# Pressure_OUTPUT.net
KiCad netlist of a schematic drawn in Altium Designer
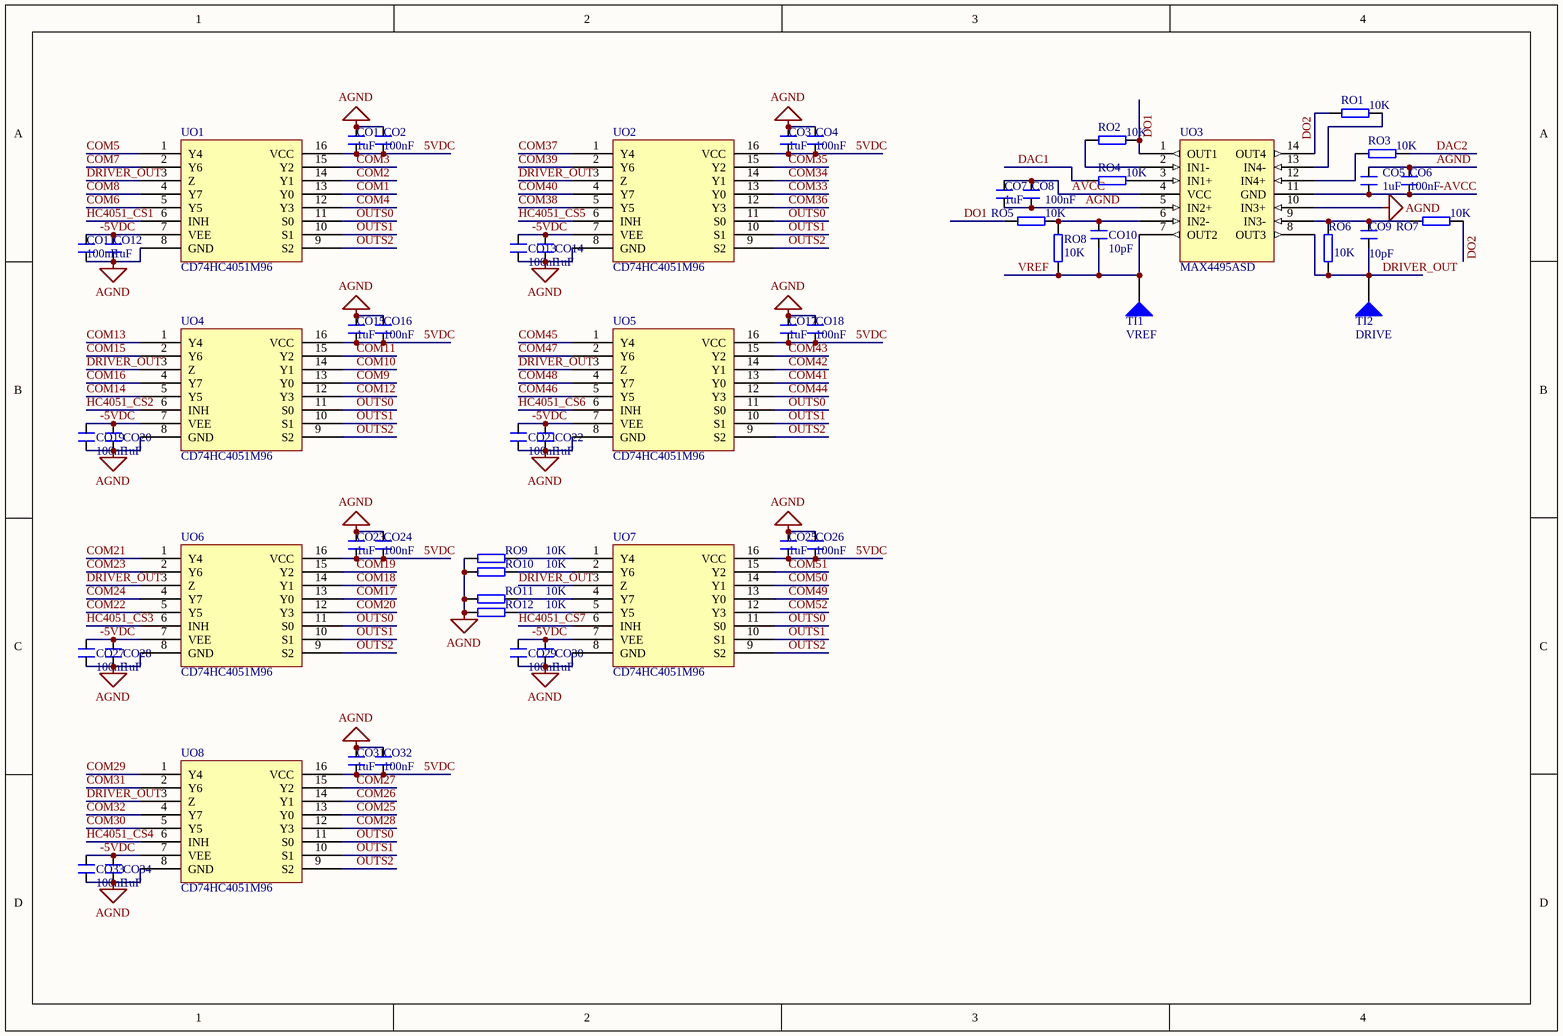
[diagram p0: Pressure_OUTPUT.SchDoc]

(export (version "E")
  (design (tool "Eeschema 10.0.6"))
  (components
    (comp (ref "CO1") (value "1uF") (footprint "C0603_HSC100") (libsource (lib "*") (part "CAP_M")))
    (comp (ref "CO2") (value "100nF") (footprint "C0603_HSC100") (libsource (lib "*") (part "CAP_M")))
    (comp (ref "CO3") (value "1uF") (footprint "C0603_HSC100") (libsource (lib "*") (part "CAP_M")))
    (comp (ref "CO4") (value "100nF") (footprint "C0603_HSC100") (libsource (lib "*") (part "CAP_M")))
    (comp (ref "CO5") (value "1uF") (footprint "C0603_HSC100") (libsource (lib "*") (part "CAP_M")))
    (comp (ref "CO6") (value "100nF") (footprint "C0603_HSC100") (libsource (lib "*") (part "CAP_M")))
    (comp (ref "CO7") (value "1uF") (footprint "C0603_HSC100") (libsource (lib "*") (part "CAP_M")))
    (comp (ref "CO8") (value "100nF") (footprint "C0603_HSC100") (libsource (lib "*") (part "CAP_M")))
    (comp (ref "CO9") (value "10pF") (footprint "C0603_HSC100") (libsource (lib "*") (part "CAP_M")))
    (comp (ref "CO10") (value "10pF") (footprint "C0603_HSC100") (libsource (lib "*") (part "CAP_M")))
    (comp (ref "CO11") (value "100nF") (footprint "C0603_HSC100") (libsource (lib "*") (part "CAP_M")))
    (comp (ref "CO12") (value "1uF") (footprint "C0603_HSC100") (libsource (lib "*") (part "CAP_M")))
    (comp (ref "CO13") (value "100nF") (footprint "C0603_HSC100") (libsource (lib "*") (part "CAP_M")))
    (comp (ref "CO14") (value "1uF") (footprint "C0603_HSC100") (libsource (lib "*") (part "CAP_M")))
    (comp (ref "CO15") (value "1uF") (footprint "C0603_HSC100") (libsource (lib "*") (part "CAP_M")))
    (comp (ref "CO16") (value "100nF") (footprint "C0603_HSC100") (libsource (lib "*") (part "CAP_M")))
    (comp (ref "CO17") (value "1uF") (footprint "C0603_HSC100") (libsource (lib "*") (part "CAP_M")))
    (comp (ref "CO18") (value "100nF") (footprint "C0603_HSC100") (libsource (lib "*") (part "CAP_M")))
    (comp (ref "CO19") (value "100nF") (footprint "C0603_HSC100") (libsource (lib "*") (part "CAP_M")))
    (comp (ref "CO20") (value "1uF") (footprint "C0603_HSC100") (libsource (lib "*") (part "CAP_M")))
    (comp (ref "CO21") (value "100nF") (footprint "C0603_HSC100") (libsource (lib "*") (part "CAP_M")))
    (comp (ref "CO22") (value "1uF") (footprint "C0603_HSC100") (libsource (lib "*") (part "CAP_M")))
    (comp (ref "CO23") (value "1uF") (footprint "C0603_HSC100") (libsource (lib "*") (part "CAP_M")))
    (comp (ref "CO24") (value "100nF") (footprint "C0603_HSC100") (libsource (lib "*") (part "CAP_M")))
    (comp (ref "CO25") (value "1uF") (footprint "C0603_HSC100") (libsource (lib "*") (part "CAP_M")))
    (comp (ref "CO26") (value "100nF") (footprint "C0603_HSC100") (libsource (lib "*") (part "CAP_M")))
    (comp (ref "CO27") (value "100nF") (footprint "C0603_HSC100") (libsource (lib "*") (part "CAP_M")))
    (comp (ref "CO28") (value "1uF") (footprint "C0603_HSC100") (libsource (lib "*") (part "CAP_M")))
    (comp (ref "CO29") (value "100nF") (footprint "C0603_HSC100") (libsource (lib "*") (part "CAP_M")))
    (comp (ref "CO30") (value "1uF") (footprint "C0603_HSC100") (libsource (lib "*") (part "CAP_M")))
    (comp (ref "CO31") (value "1uF") (footprint "C0603_HSC100") (libsource (lib "*") (part "CAP_M")))
    (comp (ref "CO32") (value "100nF") (footprint "C0603_HSC100") (libsource (lib "*") (part "CAP_M")))
    (comp (ref "CO33") (value "100nF") (footprint "C0603_HSC100") (libsource (lib "*") (part "CAP_M")))
    (comp (ref "CO34") (value "1uF") (footprint "C0603_HSC100") (libsource (lib "*") (part "CAP_M")))
    (comp (ref "RO1") (value "10K") (footprint "R0603_HSC100") (libsource (lib "MY_LIB") (part "RES")))
    (comp (ref "RO2") (value "10K") (footprint "R0603_HSC100") (libsource (lib "MY_LIB") (part "RES")))
    (comp (ref "RO3") (value "10K") (footprint "R0603_HSC100") (libsource (lib "MY_LIB") (part "RES")))
    (comp (ref "RO4") (value "10K") (footprint "R0603_HSC100") (libsource (lib "MY_LIB") (part "RES")))
    (comp (ref "RO5") (value "10K") (footprint "R0603_HSC100") (libsource (lib "*") (part "RES")))
    (comp (ref "RO6") (value "10K") (footprint "R0603_HSC100") (libsource (lib "*") (part "RES")))
    (comp (ref "RO7") (value "10K") (footprint "R0603_HSC100") (libsource (lib "*") (part "RES")))
    (comp (ref "RO8") (value "10K") (footprint "R0603_HSC100") (libsource (lib "*") (part "RES")))
    (comp (ref "RO9") (value "10K") (footprint "R0603_HSC100") (libsource (lib "*") (part "RES_M")))
    (comp (ref "RO10") (value "10K") (footprint "R0603_HSC100") (libsource (lib "*") (part "RES_M")))
    (comp (ref "RO11") (value "10K") (footprint "R0603_HSC100") (libsource (lib "*") (part "RES_M")))
    (comp (ref "RO12") (value "10K") (footprint "R0603_HSC100") (libsource (lib "*") (part "RES_M")))
    (comp (ref "TI1")
      (value "VREF")
      (footprint "TPAD-2MM")
      (description "Connector")
      (libsource (lib "MY_LIB") (part "TPAD"))
    )
    (comp (ref "TI2")
      (value "DRIVE")
      (footprint "TPAD-2MM")
      (description "Connector")
      (libsource (lib "MY_LIB") (part "TPAD"))
    )
    (comp (ref "UO1")
      (value "CD74HC4051M96")
      (footprint "SO-16")
      (description "74HC4051")
      (libsource (lib "MY_SCH") (part "74HC4051"))
    )
    (comp (ref "UO2")
      (value "CD74HC4051M96")
      (footprint "SO-16")
      (description "74HC4051")
      (libsource (lib "MY_SCH") (part "74HC4051"))
    )
    (comp (ref "UO3") (value "MAX4495ASD") (footprint "SO-14") (libsource (lib "MY_SCH") (part "LM324")))
    (comp (ref "UO4")
      (value "CD74HC4051M96")
      (footprint "SO-16")
      (description "74HC4051")
      (libsource (lib "MY_SCH") (part "74HC4051"))
    )
    (comp (ref "UO5")
      (value "CD74HC4051M96")
      (footprint "SO-16")
      (description "74HC4051")
      (libsource (lib "MY_SCH") (part "74HC4051"))
    )
    (comp (ref "UO6")
      (value "CD74HC4051M96")
      (footprint "SO-16")
      (description "74HC4051")
      (libsource (lib "MY_SCH") (part "74HC4051"))
    )
    (comp (ref "UO7")
      (value "CD74HC4051M96")
      (footprint "SO-16")
      (description "74HC4051")
      (libsource (lib "MY_SCH") (part "74HC4051"))
    )
    (comp (ref "UO8")
      (value "CD74HC4051M96")
      (footprint "SO-16")
      (description "74HC4051")
      (libsource (lib "MY_SCH") (part "74HC4051"))
    )
  )
  (nets
    (net (code "1") (name "/-5VDC") (class "Default")
      (node (ref "CO11") (pin "2") (pintype "passive"))
      (node (ref "CO12") (pin "2") (pintype "passive"))
      (node (ref "CO13") (pin "2") (pintype "passive"))
      (node (ref "CO14") (pin "2") (pintype "passive"))
      (node (ref "CO19") (pin "2") (pintype "passive"))
      (node (ref "CO20") (pin "2") (pintype "passive"))
      (node (ref "CO21") (pin "2") (pintype "passive"))
      (node (ref "CO22") (pin "2") (pintype "passive"))
      (node (ref "CO27") (pin "2") (pintype "passive"))
      (node (ref "CO28") (pin "2") (pintype "passive"))
      (node (ref "CO29") (pin "2") (pintype "passive"))
      (node (ref "CO30") (pin "2") (pintype "passive"))
      (node (ref "CO33") (pin "2") (pintype "passive"))
      (node (ref "CO34") (pin "2") (pintype "passive"))
      (node (ref "UO1") (pin "7") (pinfunction "VEE_7") (pintype "passive"))
      (node (ref "UO2") (pin "7") (pinfunction "VEE_7") (pintype "passive"))
      (node (ref "UO4") (pin "7") (pinfunction "VEE_7") (pintype "passive"))
      (node (ref "UO5") (pin "7") (pinfunction "VEE_7") (pintype "passive"))
      (node (ref "UO6") (pin "7") (pinfunction "VEE_7") (pintype "passive"))
      (node (ref "UO7") (pin "7") (pinfunction "VEE_7") (pintype "passive"))
      (node (ref "UO8") (pin "7") (pinfunction "VEE_7") (pintype "passive"))
    )
    (net (code "2") (name "/-AVCC") (class "Default")
      (node (ref "CO5") (pin "2") (pintype "passive"))
      (node (ref "CO6") (pin "2") (pintype "passive"))
      (node (ref "UO3") (pin "11") (pinfunction "GND_11") (pintype "power_in"))
    )
    (net (code "3") (name "/5VDC") (class "Default")
      (node (ref "CO1") (pin "2") (pintype "passive"))
      (node (ref "CO15") (pin "2") (pintype "passive"))
      (node (ref "CO16") (pin "2") (pintype "passive"))
      (node (ref "CO17") (pin "2") (pintype "passive"))
      (node (ref "CO18") (pin "2") (pintype "passive"))
      (node (ref "CO2") (pin "2") (pintype "passive"))
      (node (ref "CO23") (pin "2") (pintype "passive"))
      (node (ref "CO24") (pin "2") (pintype "passive"))
      (node (ref "CO25") (pin "2") (pintype "passive"))
      (node (ref "CO26") (pin "2") (pintype "passive"))
      (node (ref "CO3") (pin "2") (pintype "passive"))
      (node (ref "CO31") (pin "2") (pintype "passive"))
      (node (ref "CO32") (pin "2") (pintype "passive"))
      (node (ref "CO4") (pin "2") (pintype "passive"))
      (node (ref "UO1") (pin "16") (pinfunction "VCC_16") (pintype "tri_state"))
      (node (ref "UO2") (pin "16") (pinfunction "VCC_16") (pintype "tri_state"))
      (node (ref "UO4") (pin "16") (pinfunction "VCC_16") (pintype "tri_state"))
      (node (ref "UO5") (pin "16") (pinfunction "VCC_16") (pintype "tri_state"))
      (node (ref "UO6") (pin "16") (pinfunction "VCC_16") (pintype "tri_state"))
      (node (ref "UO7") (pin "16") (pinfunction "VCC_16") (pintype "tri_state"))
      (node (ref "UO8") (pin "16") (pinfunction "VCC_16") (pintype "tri_state"))
    )
    (net (code "4") (name "/AVCC") (class "Default")
      (node (ref "CO7") (pin "1") (pintype "passive"))
      (node (ref "CO8") (pin "1") (pintype "passive"))
      (node (ref "UO3") (pin "4") (pinfunction "VCC_4") (pintype "power_in"))
    )
    (net (code "5") (name "/COM1") (class "Default")
      (node (ref "UO1") (pin "13") (pinfunction "Y0_13") (pintype "tri_state"))
    )
    (net (code "6") (name "/COM2") (class "Default")
      (node (ref "UO1") (pin "14") (pinfunction "Y1_14") (pintype "tri_state"))
    )
    (net (code "7") (name "/COM3") (class "Default")
      (node (ref "UO1") (pin "15") (pinfunction "Y2_15") (pintype "tri_state"))
    )
    (net (code "8") (name "/COM4") (class "Default")
      (node (ref "UO1") (pin "12") (pinfunction "Y3_12") (pintype "tri_state"))
    )
    (net (code "9") (name "/COM5") (class "Default")
      (node (ref "UO1") (pin "1") (pinfunction "Y4_1") (pintype "passive"))
    )
    (net (code "10") (name "/COM6") (class "Default")
      (node (ref "UO1") (pin "5") (pinfunction "Y5_5") (pintype "passive"))
    )
    (net (code "11") (name "/COM7") (class "Default")
      (node (ref "UO1") (pin "2") (pinfunction "Y6_2") (pintype "passive"))
    )
    (net (code "12") (name "/COM8") (class "Default")
      (node (ref "UO1") (pin "4") (pinfunction "Y7_4") (pintype "passive"))
    )
    (net (code "13") (name "/COM9") (class "Default")
      (node (ref "UO4") (pin "13") (pinfunction "Y0_13") (pintype "tri_state"))
    )
    (net (code "14") (name "/COM10") (class "Default")
      (node (ref "UO4") (pin "14") (pinfunction "Y1_14") (pintype "tri_state"))
    )
    (net (code "15") (name "/COM11") (class "Default")
      (node (ref "UO4") (pin "15") (pinfunction "Y2_15") (pintype "tri_state"))
    )
    (net (code "16") (name "/COM12") (class "Default")
      (node (ref "UO4") (pin "12") (pinfunction "Y3_12") (pintype "tri_state"))
    )
    (net (code "17") (name "/COM13") (class "Default")
      (node (ref "UO4") (pin "1") (pinfunction "Y4_1") (pintype "passive"))
    )
    (net (code "18") (name "/COM14") (class "Default")
      (node (ref "UO4") (pin "5") (pinfunction "Y5_5") (pintype "passive"))
    )
    (net (code "19") (name "/COM15") (class "Default")
      (node (ref "UO4") (pin "2") (pinfunction "Y6_2") (pintype "passive"))
    )
    (net (code "20") (name "/COM16") (class "Default")
      (node (ref "UO4") (pin "4") (pinfunction "Y7_4") (pintype "passive"))
    )
    (net (code "21") (name "/COM17") (class "Default")
      (node (ref "UO6") (pin "13") (pinfunction "Y0_13") (pintype "tri_state"))
    )
    (net (code "22") (name "/COM18") (class "Default")
      (node (ref "UO6") (pin "14") (pinfunction "Y1_14") (pintype "tri_state"))
    )
    (net (code "23") (name "/COM19") (class "Default")
      (node (ref "UO6") (pin "15") (pinfunction "Y2_15") (pintype "tri_state"))
    )
    (net (code "24") (name "/COM20") (class "Default")
      (node (ref "UO6") (pin "12") (pinfunction "Y3_12") (pintype "tri_state"))
    )
    (net (code "25") (name "/COM21") (class "Default")
      (node (ref "UO6") (pin "1") (pinfunction "Y4_1") (pintype "passive"))
    )
    (net (code "26") (name "/COM22") (class "Default")
      (node (ref "UO6") (pin "5") (pinfunction "Y5_5") (pintype "passive"))
    )
    (net (code "27") (name "/COM23") (class "Default")
      (node (ref "UO6") (pin "2") (pinfunction "Y6_2") (pintype "passive"))
    )
    (net (code "28") (name "/COM24") (class "Default")
      (node (ref "UO6") (pin "4") (pinfunction "Y7_4") (pintype "passive"))
    )
    (net (code "29") (name "/COM25") (class "Default")
      (node (ref "UO8") (pin "13") (pinfunction "Y0_13") (pintype "tri_state"))
    )
    (net (code "30") (name "/COM26") (class "Default")
      (node (ref "UO8") (pin "14") (pinfunction "Y1_14") (pintype "tri_state"))
    )
    (net (code "31") (name "/COM27") (class "Default")
      (node (ref "UO8") (pin "15") (pinfunction "Y2_15") (pintype "tri_state"))
    )
    (net (code "32") (name "/COM28") (class "Default")
      (node (ref "UO8") (pin "12") (pinfunction "Y3_12") (pintype "tri_state"))
    )
    (net (code "33") (name "/COM29") (class "Default")
      (node (ref "UO8") (pin "1") (pinfunction "Y4_1") (pintype "passive"))
    )
    (net (code "34") (name "/COM30") (class "Default")
      (node (ref "UO8") (pin "5") (pinfunction "Y5_5") (pintype "passive"))
    )
    (net (code "35") (name "/COM31") (class "Default")
      (node (ref "UO8") (pin "2") (pinfunction "Y6_2") (pintype "passive"))
    )
    (net (code "36") (name "/COM32") (class "Default")
      (node (ref "UO8") (pin "4") (pinfunction "Y7_4") (pintype "passive"))
    )
    (net (code "37") (name "/COM33") (class "Default")
      (node (ref "UO2") (pin "13") (pinfunction "Y0_13") (pintype "tri_state"))
    )
    (net (code "38") (name "/COM34") (class "Default")
      (node (ref "UO2") (pin "14") (pinfunction "Y1_14") (pintype "tri_state"))
    )
    (net (code "39") (name "/COM35") (class "Default")
      (node (ref "UO2") (pin "15") (pinfunction "Y2_15") (pintype "tri_state"))
    )
    (net (code "40") (name "/COM36") (class "Default")
      (node (ref "UO2") (pin "12") (pinfunction "Y3_12") (pintype "tri_state"))
    )
    (net (code "41") (name "/COM37") (class "Default")
      (node (ref "UO2") (pin "1") (pinfunction "Y4_1") (pintype "passive"))
    )
    (net (code "42") (name "/COM38") (class "Default")
      (node (ref "UO2") (pin "5") (pinfunction "Y5_5") (pintype "passive"))
    )
    (net (code "43") (name "/COM39") (class "Default")
      (node (ref "UO2") (pin "2") (pinfunction "Y6_2") (pintype "passive"))
    )
    (net (code "44") (name "/COM40") (class "Default")
      (node (ref "UO2") (pin "4") (pinfunction "Y7_4") (pintype "passive"))
    )
    (net (code "45") (name "/COM41") (class "Default")
      (node (ref "UO5") (pin "13") (pinfunction "Y0_13") (pintype "tri_state"))
    )
    (net (code "46") (name "/COM42") (class "Default")
      (node (ref "UO5") (pin "14") (pinfunction "Y1_14") (pintype "tri_state"))
    )
    (net (code "47") (name "/COM43") (class "Default")
      (node (ref "UO5") (pin "15") (pinfunction "Y2_15") (pintype "tri_state"))
    )
    (net (code "48") (name "/COM44") (class "Default")
      (node (ref "UO5") (pin "12") (pinfunction "Y3_12") (pintype "tri_state"))
    )
    (net (code "49") (name "/COM45") (class "Default")
      (node (ref "UO5") (pin "1") (pinfunction "Y4_1") (pintype "passive"))
    )
    (net (code "50") (name "/COM46") (class "Default")
      (node (ref "UO5") (pin "5") (pinfunction "Y5_5") (pintype "passive"))
    )
    (net (code "51") (name "/COM47") (class "Default")
      (node (ref "UO5") (pin "2") (pinfunction "Y6_2") (pintype "passive"))
    )
    (net (code "52") (name "/COM48") (class "Default")
      (node (ref "UO5") (pin "4") (pinfunction "Y7_4") (pintype "passive"))
    )
    (net (code "53") (name "/COM49") (class "Default")
      (node (ref "UO7") (pin "13") (pinfunction "Y0_13") (pintype "tri_state"))
    )
    (net (code "54") (name "/COM50") (class "Default")
      (node (ref "UO7") (pin "14") (pinfunction "Y1_14") (pintype "tri_state"))
    )
    (net (code "55") (name "/COM51") (class "Default")
      (node (ref "UO7") (pin "15") (pinfunction "Y2_15") (pintype "tri_state"))
    )
    (net (code "56") (name "/COM52") (class "Default")
      (node (ref "UO7") (pin "12") (pinfunction "Y3_12") (pintype "tri_state"))
    )
    (net (code "57") (name "/DAC1") (class "Default") (node (ref "RO4") (pin "1") (pintype "passive")))
    (net (code "58") (name "/DAC2") (class "Default") (node (ref "RO3") (pin "1") (pintype "passive")))
    (net (code "59") (name "/DO1") (class "Default")
      (node (ref "RO2") (pin "2") (pintype "passive"))
      (node (ref "RO5") (pin "2") (pintype "passive"))
      (node (ref "UO3") (pin "1") (pinfunction "OUT1_1") (pintype "output"))
    )
    (net (code "60") (name "/DO2") (class "Default")
      (node (ref "RO1") (pin "2") (pintype "passive"))
      (node (ref "RO7") (pin "1") (pintype "passive"))
      (node (ref "UO3") (pin "14") (pinfunction "OUT4_14") (pintype "output"))
    )
    (net (code "61") (name "/DRIVER_OUT") (class "Default")
      (node (ref "CO9") (pin "2") (pintype "passive"))
      (node (ref "RO6") (pin "2") (pintype "passive"))
      (node (ref "TI2") (pin "1") (pinfunction "1_1") (pintype "passive"))
      (node (ref "UO1") (pin "3") (pinfunction "Z_3") (pintype "passive"))
      (node (ref "UO2") (pin "3") (pinfunction "Z_3") (pintype "passive"))
      (node (ref "UO3") (pin "8") (pinfunction "OUT3_8") (pintype "output"))
      (node (ref "UO4") (pin "3") (pinfunction "Z_3") (pintype "passive"))
      (node (ref "UO5") (pin "3") (pinfunction "Z_3") (pintype "passive"))
      (node (ref "UO6") (pin "3") (pinfunction "Z_3") (pintype "passive"))
      (node (ref "UO7") (pin "3") (pinfunction "Z_3") (pintype "passive"))
      (node (ref "UO8") (pin "3") (pinfunction "Z_3") (pintype "passive"))
    )
    (net (code "62") (name "/HC4051_CS1") (class "Default")
      (node (ref "UO1") (pin "6") (pinfunction "INH_6") (pintype "passive"))
    )
    (net (code "63") (name "/HC4051_CS2") (class "Default")
      (node (ref "UO4") (pin "6") (pinfunction "INH_6") (pintype "passive"))
    )
    (net (code "64") (name "/HC4051_CS3") (class "Default")
      (node (ref "UO6") (pin "6") (pinfunction "INH_6") (pintype "passive"))
    )
    (net (code "65") (name "/HC4051_CS4") (class "Default")
      (node (ref "UO8") (pin "6") (pinfunction "INH_6") (pintype "passive"))
    )
    (net (code "66") (name "/HC4051_CS5") (class "Default")
      (node (ref "UO2") (pin "6") (pinfunction "INH_6") (pintype "passive"))
    )
    (net (code "67") (name "/HC4051_CS6") (class "Default")
      (node (ref "UO5") (pin "6") (pinfunction "INH_6") (pintype "passive"))
    )
    (net (code "68") (name "/HC4051_CS7") (class "Default")
      (node (ref "UO7") (pin "6") (pinfunction "INH_6") (pintype "passive"))
    )
    (net (code "69") (name "/OUTS0") (class "Default")
      (node (ref "UO1") (pin "11") (pinfunction "S0_11") (pintype "tri_state"))
      (node (ref "UO2") (pin "11") (pinfunction "S0_11") (pintype "tri_state"))
      (node (ref "UO4") (pin "11") (pinfunction "S0_11") (pintype "tri_state"))
      (node (ref "UO5") (pin "11") (pinfunction "S0_11") (pintype "tri_state"))
      (node (ref "UO6") (pin "11") (pinfunction "S0_11") (pintype "tri_state"))
      (node (ref "UO7") (pin "11") (pinfunction "S0_11") (pintype "tri_state"))
      (node (ref "UO8") (pin "11") (pinfunction "S0_11") (pintype "tri_state"))
    )
    (net (code "70") (name "/OUTS1") (class "Default")
      (node (ref "UO1") (pin "10") (pinfunction "S1_10") (pintype "tri_state"))
      (node (ref "UO2") (pin "10") (pinfunction "S1_10") (pintype "tri_state"))
      (node (ref "UO4") (pin "10") (pinfunction "S1_10") (pintype "tri_state"))
      (node (ref "UO5") (pin "10") (pinfunction "S1_10") (pintype "tri_state"))
      (node (ref "UO6") (pin "10") (pinfunction "S1_10") (pintype "tri_state"))
      (node (ref "UO7") (pin "10") (pinfunction "S1_10") (pintype "tri_state"))
      (node (ref "UO8") (pin "10") (pinfunction "S1_10") (pintype "tri_state"))
    )
    (net (code "71") (name "/OUTS2") (class "Default")
      (node (ref "UO1") (pin "9") (pinfunction "S2_9") (pintype "tri_state"))
      (node (ref "UO2") (pin "9") (pinfunction "S2_9") (pintype "tri_state"))
      (node (ref "UO4") (pin "9") (pinfunction "S2_9") (pintype "tri_state"))
      (node (ref "UO5") (pin "9") (pinfunction "S2_9") (pintype "tri_state"))
      (node (ref "UO6") (pin "9") (pinfunction "S2_9") (pintype "tri_state"))
      (node (ref "UO7") (pin "9") (pinfunction "S2_9") (pintype "tri_state"))
      (node (ref "UO8") (pin "9") (pinfunction "S2_9") (pintype "tri_state"))
    )
    (net (code "72") (name "/VREF") (class "Default")
      (node (ref "CO10") (pin "2") (pintype "passive"))
      (node (ref "RO8") (pin "1") (pintype "passive"))
      (node (ref "TI1") (pin "1") (pinfunction "1_1") (pintype "passive"))
      (node (ref "UO3") (pin "7") (pinfunction "OUT2_7") (pintype "output"))
    )
    (net (code "73") (name "AGND") (class "Default")
      (node (ref "CO1") (pin "1") (pintype "passive"))
      (node (ref "CO11") (pin "1") (pintype "passive"))
      (node (ref "CO12") (pin "1") (pintype "passive"))
      (node (ref "CO13") (pin "1") (pintype "passive"))
      (node (ref "CO14") (pin "1") (pintype "passive"))
      (node (ref "CO15") (pin "1") (pintype "passive"))
      (node (ref "CO16") (pin "1") (pintype "passive"))
      (node (ref "CO17") (pin "1") (pintype "passive"))
      (node (ref "CO18") (pin "1") (pintype "passive"))
      (node (ref "CO19") (pin "1") (pintype "passive"))
      (node (ref "CO2") (pin "1") (pintype "passive"))
      (node (ref "CO20") (pin "1") (pintype "passive"))
      (node (ref "CO21") (pin "1") (pintype "passive"))
      (node (ref "CO22") (pin "1") (pintype "passive"))
      (node (ref "CO23") (pin "1") (pintype "passive"))
      (node (ref "CO24") (pin "1") (pintype "passive"))
      (node (ref "CO25") (pin "1") (pintype "passive"))
      (node (ref "CO26") (pin "1") (pintype "passive"))
      (node (ref "CO27") (pin "1") (pintype "passive"))
      (node (ref "CO28") (pin "1") (pintype "passive"))
      (node (ref "CO29") (pin "1") (pintype "passive"))
      (node (ref "CO3") (pin "1") (pintype "passive"))
      (node (ref "CO30") (pin "1") (pintype "passive"))
      (node (ref "CO31") (pin "1") (pintype "passive"))
      (node (ref "CO32") (pin "1") (pintype "passive"))
      (node (ref "CO33") (pin "1") (pintype "passive"))
      (node (ref "CO34") (pin "1") (pintype "passive"))
      (node (ref "CO4") (pin "1") (pintype "passive"))
      (node (ref "CO5") (pin "1") (pintype "passive"))
      (node (ref "CO6") (pin "1") (pintype "passive"))
      (node (ref "CO7") (pin "2") (pintype "passive"))
      (node (ref "CO8") (pin "2") (pintype "passive"))
      (node (ref "RO10") (pin "1") (pintype "passive"))
      (node (ref "RO11") (pin "1") (pintype "passive"))
      (node (ref "RO12") (pin "1") (pintype "passive"))
      (node (ref "RO9") (pin "1") (pintype "passive"))
      (node (ref "UO1") (pin "8") (pinfunction "GND_8") (pintype "tri_state"))
      (node (ref "UO2") (pin "8") (pinfunction "GND_8") (pintype "tri_state"))
      (node (ref "UO3") (pin "10") (pinfunction "IN3+_10") (pintype "input"))
      (node (ref "UO3") (pin "5") (pinfunction "IN2+_5") (pintype "input"))
      (node (ref "UO4") (pin "8") (pinfunction "GND_8") (pintype "tri_state"))
      (node (ref "UO5") (pin "8") (pinfunction "GND_8") (pintype "tri_state"))
      (node (ref "UO6") (pin "8") (pinfunction "GND_8") (pintype "tri_state"))
      (node (ref "UO7") (pin "8") (pinfunction "GND_8") (pintype "tri_state"))
      (node (ref "UO8") (pin "8") (pinfunction "GND_8") (pintype "tri_state"))
    )
    (net (code "74") (name "Net-(UO3-IN1+)") (class "Default")
      (node (ref "RO4") (pin "2") (pintype "passive"))
      (node (ref "UO3") (pin "3") (pinfunction "IN1+_3") (pintype "input"))
    )
    (net (code "75") (name "Net-(UO3-IN1-)") (class "Default")
      (node (ref "RO2") (pin "1") (pintype "passive"))
      (node (ref "UO3") (pin "2") (pinfunction "IN1-_2") (pintype "input"))
    )
    (net (code "76") (name "Net-(UO3-IN2-)") (class "Default")
      (node (ref "CO10") (pin "1") (pintype "passive"))
      (node (ref "RO5") (pin "1") (pintype "passive"))
      (node (ref "RO8") (pin "2") (pintype "passive"))
      (node (ref "UO3") (pin "6") (pinfunction "IN2-_6") (pintype "input"))
    )
    (net (code "77") (name "Net-(UO3-IN3-)") (class "Default")
      (node (ref "CO9") (pin "1") (pintype "passive"))
      (node (ref "RO6") (pin "1") (pintype "passive"))
      (node (ref "RO7") (pin "2") (pintype "passive"))
      (node (ref "UO3") (pin "9") (pinfunction "IN3-_9") (pintype "input"))
    )
    (net (code "78") (name "Net-(UO3-IN4+)") (class "Default")
      (node (ref "RO3") (pin "2") (pintype "passive"))
      (node (ref "UO3") (pin "12") (pinfunction "IN4+_12") (pintype "input"))
    )
    (net (code "79") (name "Net-(UO3-IN4-)") (class "Default")
      (node (ref "RO1") (pin "1") (pintype "passive"))
      (node (ref "UO3") (pin "13") (pinfunction "IN4-_13") (pintype "input"))
    )
    (net (code "80") (name "Net-(UO7-Y4)") (class "Default")
      (node (ref "RO9") (pin "2") (pintype "passive"))
      (node (ref "UO7") (pin "1") (pinfunction "Y4_1") (pintype "passive"))
    )
    (net (code "81") (name "Net-(UO7-Y5)") (class "Default")
      (node (ref "RO12") (pin "2") (pintype "passive"))
      (node (ref "UO7") (pin "5") (pinfunction "Y5_5") (pintype "passive"))
    )
    (net (code "82") (name "Net-(UO7-Y6)") (class "Default")
      (node (ref "RO10") (pin "2") (pintype "passive"))
      (node (ref "UO7") (pin "2") (pinfunction "Y6_2") (pintype "passive"))
    )
    (net (code "83") (name "Net-(UO7-Y7)") (class "Default")
      (node (ref "RO11") (pin "2") (pintype "passive"))
      (node (ref "UO7") (pin "4") (pinfunction "Y7_4") (pintype "passive"))
    )
  )
)
